# Sheet1.net
KiCad netlist of a schematic drawn in Altium Designer
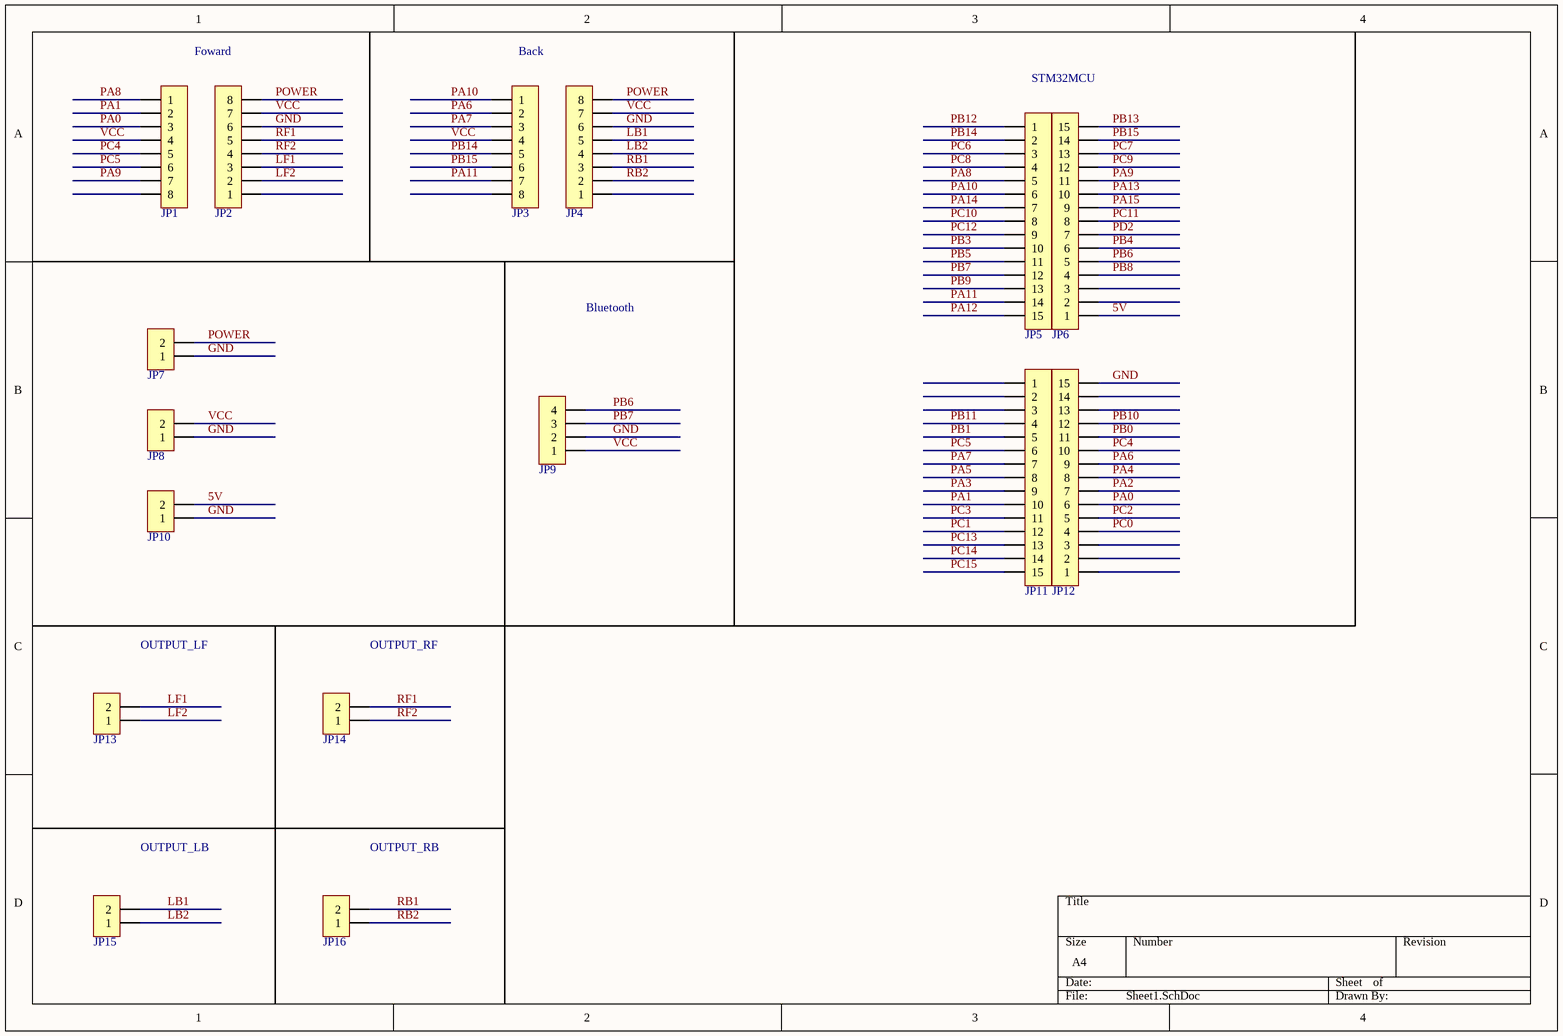
[diagram p0: Sheet1.SchDoc]

(export (version "E")
  (design (tool "Eeschema 10.0.6"))
  (components
    (comp (ref "JP1")
      (value "HDR-1X8")
      (footprint "Fe-HDR1X8/2.54-S")
      (description "8P接插件")
      (fields (field (name "版权归属") "源创客"))
      (libsource (lib "4.5   - 接插件-脚距2.54") (part "Header 8"))
    )
    (comp (ref "JP2")
      (value "HDR-1X8")
      (footprint "Fe-HDR1X8/2.54-S")
      (description "8P接插件")
      (fields (field (name "版权归属") "源创客"))
      (libsource (lib "") (part "Header 8_1"))
    )
    (comp (ref "JP3")
      (value "HDR-1X8")
      (footprint "Fe-HDR1X8/2.54-S")
      (description "8P接插件")
      (fields (field (name "版权归属") "源创客"))
      (libsource (lib "4.5   - 接插件-脚距2.54") (part "Header 8"))
    )
    (comp (ref "JP4")
      (value "HDR-1X8")
      (footprint "Fe-HDR1X8/2.54-S")
      (description "8P接插件")
      (fields (field (name "版权归属") "源创客"))
      (libsource (lib "") (part "Header 8_1"))
    )
    (comp (ref "JP5")
      (value "HDR-1X15")
      (footprint "Fe-HDR1X15/2.54-S")
      (description "15P接插件")
      (fields (field (name "版权归属") "源创客"))
      (libsource (lib "") (part "Header 15_1"))
    )
    (comp (ref "JP6")
      (value "HDR-1X15")
      (footprint "Fe-HDR1X15/2.54-S")
      (description "15P接插件")
      (fields (field (name "版权归属") "源创客"))
      (libsource (lib "4.5   - 接插件-脚距2.54") (part "Header 15"))
    )
    (comp (ref "JP7")
      (value "HDR-1X2")
      (footprint "Fe-HDR1X2/2.54-S")
      (description "2P接插件")
      (fields (field (name "版权归属") "源创客"))
      (libsource (lib "4.5   - 接插件-脚距2.54") (part "Header 2"))
    )
    (comp (ref "JP8")
      (value "HDR-1X2")
      (footprint "Fe-HDR1X2/2.54-S")
      (description "2P接插件")
      (fields (field (name "版权归属") "源创客"))
      (libsource (lib "4.5   - 接插件-脚距2.54") (part "Header 2"))
    )
    (comp (ref "JP9")
      (value "HDR-1X4")
      (footprint "Fe-HDR1X4/2.54-S")
      (description "4P接插件")
      (fields (field (name "版权归属") "源创客"))
      (libsource (lib "4.5   - 接插件-脚距2.54") (part "Header 4"))
    )
    (comp (ref "JP10")
      (value "HDR-1X2")
      (footprint "Fe-HDR1X2/2.54-S")
      (description "2P接插件")
      (fields (field (name "版权归属") "源创客"))
      (libsource (lib "4.5   - 接插件-脚距2.54") (part "Header 2"))
    )
    (comp (ref "JP11")
      (value "HDR-1X15")
      (footprint "Fe-HDR1X15/2.54-S")
      (description "15P接插件")
      (fields (field (name "版权归属") "源创客"))
      (libsource (lib "") (part "Header 15_1"))
    )
    (comp (ref "JP12")
      (value "HDR-1X15")
      (footprint "Fe-HDR1X15/2.54-S")
      (description "15P接插件")
      (fields (field (name "版权归属") "源创客"))
      (libsource (lib "4.5   - 接插件-脚距2.54") (part "Header 15"))
    )
    (comp (ref "JP13")
      (value "HDR-1X2")
      (footprint "Fe-HDR1X2/2.54-S")
      (description "2P接插件")
      (fields (field (name "版权归属") "源创客"))
      (libsource (lib "4.5   - 接插件-脚距2.54") (part "Header 2"))
    )
    (comp (ref "JP14")
      (value "HDR-1X2")
      (footprint "Fe-HDR1X2/2.54-S")
      (description "2P接插件")
      (fields (field (name "版权归属") "源创客"))
      (libsource (lib "4.5   - 接插件-脚距2.54") (part "Header 2"))
    )
    (comp (ref "JP15")
      (value "HDR-1X2")
      (footprint "Fe-HDR1X2/2.54-S")
      (description "2P接插件")
      (fields (field (name "版权归属") "源创客"))
      (libsource (lib "4.5   - 接插件-脚距2.54") (part "Header 2"))
    )
    (comp (ref "JP16")
      (value "HDR-1X2")
      (footprint "Fe-HDR1X2/2.54-S")
      (description "2P接插件")
      (fields (field (name "版权归属") "源创客"))
      (libsource (lib "4.5   - 接插件-脚距2.54") (part "Header 2"))
    )
  )
  (nets
    (net (code "1") (name "/5V") (class "Default")
      (node (ref "JP10") (pin "2") (pinfunction "2_2") (pintype "passive"))
      (node (ref "JP6") (pin "1") (pinfunction "1_1") (pintype "passive"))
    )
    (net (code "2") (name "/GND") (class "Default")
      (node (ref "JP10") (pin "1") (pinfunction "1_1") (pintype "passive"))
      (node (ref "JP12") (pin "15") (pinfunction "15_15") (pintype "passive"))
      (node (ref "JP2") (pin "6") (pinfunction "6_6") (pintype "passive"))
      (node (ref "JP4") (pin "6") (pinfunction "6_6") (pintype "passive"))
      (node (ref "JP7") (pin "1") (pinfunction "1_1") (pintype "passive"))
      (node (ref "JP8") (pin "1") (pinfunction "1_1") (pintype "passive"))
      (node (ref "JP9") (pin "2") (pinfunction "2_2") (pintype "passive"))
    )
    (net (code "3") (name "/LB1") (class "Default")
      (node (ref "JP15") (pin "2") (pinfunction "2_2") (pintype "passive"))
      (node (ref "JP4") (pin "5") (pinfunction "5_5") (pintype "passive"))
    )
    (net (code "4") (name "/LB2") (class "Default")
      (node (ref "JP15") (pin "1") (pinfunction "1_1") (pintype "passive"))
      (node (ref "JP4") (pin "4") (pinfunction "4_4") (pintype "passive"))
    )
    (net (code "5") (name "/LF1") (class "Default")
      (node (ref "JP13") (pin "2") (pinfunction "2_2") (pintype "passive"))
      (node (ref "JP2") (pin "3") (pinfunction "3_3") (pintype "passive"))
    )
    (net (code "6") (name "/LF2") (class "Default")
      (node (ref "JP13") (pin "1") (pinfunction "1_1") (pintype "passive"))
      (node (ref "JP2") (pin "2") (pinfunction "2_2") (pintype "passive"))
    )
    (net (code "7") (name "/PA0") (class "Default")
      (node (ref "JP1") (pin "3") (pinfunction "3_3") (pintype "passive"))
      (node (ref "JP12") (pin "6") (pinfunction "6_6") (pintype "passive"))
    )
    (net (code "8") (name "/PA1") (class "Default")
      (node (ref "JP1") (pin "2") (pinfunction "2_2") (pintype "passive"))
      (node (ref "JP11") (pin "10") (pinfunction "10_10") (pintype "passive"))
    )
    (net (code "9") (name "/PA2") (class "Default")
      (node (ref "JP12") (pin "7") (pinfunction "7_7") (pintype "passive"))
    )
    (net (code "10") (name "/PA3") (class "Default")
      (node (ref "JP11") (pin "9") (pinfunction "9_9") (pintype "passive"))
    )
    (net (code "11") (name "/PA4") (class "Default")
      (node (ref "JP12") (pin "8") (pinfunction "8_8") (pintype "passive"))
    )
    (net (code "12") (name "/PA5") (class "Default")
      (node (ref "JP11") (pin "8") (pinfunction "8_8") (pintype "passive"))
    )
    (net (code "13") (name "/PA6") (class "Default")
      (node (ref "JP12") (pin "9") (pinfunction "9_9") (pintype "passive"))
      (node (ref "JP3") (pin "2") (pinfunction "2_2") (pintype "passive"))
    )
    (net (code "14") (name "/PA7") (class "Default")
      (node (ref "JP11") (pin "7") (pinfunction "7_7") (pintype "passive"))
      (node (ref "JP3") (pin "3") (pinfunction "3_3") (pintype "passive"))
    )
    (net (code "15") (name "/PA8") (class "Default")
      (node (ref "JP1") (pin "1") (pinfunction "1_1") (pintype "passive"))
      (node (ref "JP5") (pin "5") (pinfunction "5_5") (pintype "passive"))
    )
    (net (code "16") (name "/PA9") (class "Default")
      (node (ref "JP1") (pin "7") (pinfunction "7_7") (pintype "passive"))
      (node (ref "JP6") (pin "11") (pinfunction "11_11") (pintype "passive"))
    )
    (net (code "17") (name "/PA10") (class "Default")
      (node (ref "JP3") (pin "1") (pinfunction "1_1") (pintype "passive"))
      (node (ref "JP5") (pin "6") (pinfunction "6_6") (pintype "passive"))
    )
    (net (code "18") (name "/PA11") (class "Default")
      (node (ref "JP3") (pin "7") (pinfunction "7_7") (pintype "passive"))
      (node (ref "JP5") (pin "14") (pinfunction "14_14") (pintype "passive"))
    )
    (net (code "19") (name "/PA12") (class "Default")
      (node (ref "JP5") (pin "15") (pinfunction "15_15") (pintype "passive"))
    )
    (net (code "20") (name "/PA13") (class "Default")
      (node (ref "JP6") (pin "10") (pinfunction "10_10") (pintype "passive"))
    )
    (net (code "21") (name "/PA14") (class "Default")
      (node (ref "JP5") (pin "7") (pinfunction "7_7") (pintype "passive"))
    )
    (net (code "22") (name "/PA15") (class "Default")
      (node (ref "JP6") (pin "9") (pinfunction "9_9") (pintype "passive"))
    )
    (net (code "23") (name "/PB0") (class "Default")
      (node (ref "JP12") (pin "11") (pinfunction "11_11") (pintype "passive"))
    )
    (net (code "24") (name "/PB1") (class "Default")
      (node (ref "JP11") (pin "5") (pinfunction "5_5") (pintype "passive"))
    )
    (net (code "25") (name "/PB3") (class "Default")
      (node (ref "JP5") (pin "10") (pinfunction "10_10") (pintype "passive"))
    )
    (net (code "26") (name "/PB4") (class "Default")
      (node (ref "JP6") (pin "6") (pinfunction "6_6") (pintype "passive"))
    )
    (net (code "27") (name "/PB5") (class "Default")
      (node (ref "JP5") (pin "11") (pinfunction "11_11") (pintype "passive"))
    )
    (net (code "28") (name "/PB6") (class "Default")
      (node (ref "JP6") (pin "5") (pinfunction "5_5") (pintype "passive"))
      (node (ref "JP9") (pin "4") (pinfunction "4_4") (pintype "passive"))
    )
    (net (code "29") (name "/PB7") (class "Default")
      (node (ref "JP5") (pin "12") (pinfunction "12_12") (pintype "passive"))
      (node (ref "JP9") (pin "3") (pinfunction "3_3") (pintype "passive"))
    )
    (net (code "30") (name "/PB8") (class "Default")
      (node (ref "JP6") (pin "4") (pinfunction "4_4") (pintype "passive"))
    )
    (net (code "31") (name "/PB9") (class "Default")
      (node (ref "JP5") (pin "13") (pinfunction "13_13") (pintype "passive"))
    )
    (net (code "32") (name "/PB10") (class "Default")
      (node (ref "JP12") (pin "12") (pinfunction "12_12") (pintype "passive"))
    )
    (net (code "33") (name "/PB11") (class "Default")
      (node (ref "JP11") (pin "4") (pinfunction "4_4") (pintype "passive"))
    )
    (net (code "34") (name "/PB12") (class "Default")
      (node (ref "JP5") (pin "1") (pinfunction "1_1") (pintype "passive"))
    )
    (net (code "35") (name "/PB13") (class "Default")
      (node (ref "JP6") (pin "15") (pinfunction "15_15") (pintype "passive"))
    )
    (net (code "36") (name "/PB14") (class "Default")
      (node (ref "JP3") (pin "5") (pinfunction "5_5") (pintype "passive"))
      (node (ref "JP5") (pin "2") (pinfunction "2_2") (pintype "passive"))
    )
    (net (code "37") (name "/PB15") (class "Default")
      (node (ref "JP3") (pin "6") (pinfunction "6_6") (pintype "passive"))
      (node (ref "JP6") (pin "14") (pinfunction "14_14") (pintype "passive"))
    )
    (net (code "38") (name "/PC0") (class "Default")
      (node (ref "JP12") (pin "4") (pinfunction "4_4") (pintype "passive"))
    )
    (net (code "39") (name "/PC1") (class "Default")
      (node (ref "JP11") (pin "12") (pinfunction "12_12") (pintype "passive"))
    )
    (net (code "40") (name "/PC2") (class "Default")
      (node (ref "JP12") (pin "5") (pinfunction "5_5") (pintype "passive"))
    )
    (net (code "41") (name "/PC3") (class "Default")
      (node (ref "JP11") (pin "11") (pinfunction "11_11") (pintype "passive"))
    )
    (net (code "42") (name "/PC4") (class "Default")
      (node (ref "JP1") (pin "5") (pinfunction "5_5") (pintype "passive"))
      (node (ref "JP12") (pin "10") (pinfunction "10_10") (pintype "passive"))
    )
    (net (code "43") (name "/PC5") (class "Default")
      (node (ref "JP1") (pin "6") (pinfunction "6_6") (pintype "passive"))
      (node (ref "JP11") (pin "6") (pinfunction "6_6") (pintype "passive"))
    )
    (net (code "44") (name "/PC6") (class "Default")
      (node (ref "JP5") (pin "3") (pinfunction "3_3") (pintype "passive"))
    )
    (net (code "45") (name "/PC7") (class "Default")
      (node (ref "JP6") (pin "13") (pinfunction "13_13") (pintype "passive"))
    )
    (net (code "46") (name "/PC8") (class "Default")
      (node (ref "JP5") (pin "4") (pinfunction "4_4") (pintype "passive"))
    )
    (net (code "47") (name "/PC9") (class "Default")
      (node (ref "JP6") (pin "12") (pinfunction "12_12") (pintype "passive"))
    )
    (net (code "48") (name "/PC10") (class "Default")
      (node (ref "JP5") (pin "8") (pinfunction "8_8") (pintype "passive"))
    )
    (net (code "49") (name "/PC11") (class "Default")
      (node (ref "JP6") (pin "8") (pinfunction "8_8") (pintype "passive"))
    )
    (net (code "50") (name "/PC12") (class "Default")
      (node (ref "JP5") (pin "9") (pinfunction "9_9") (pintype "passive"))
    )
    (net (code "51") (name "/PC13") (class "Default")
      (node (ref "JP11") (pin "13") (pinfunction "13_13") (pintype "passive"))
    )
    (net (code "52") (name "/PC14") (class "Default")
      (node (ref "JP11") (pin "14") (pinfunction "14_14") (pintype "passive"))
    )
    (net (code "53") (name "/PC15") (class "Default")
      (node (ref "JP11") (pin "15") (pinfunction "15_15") (pintype "passive"))
    )
    (net (code "54") (name "/PD2") (class "Default")
      (node (ref "JP6") (pin "7") (pinfunction "7_7") (pintype "passive"))
    )
    (net (code "55") (name "/POWER") (class "Default")
      (node (ref "JP2") (pin "8") (pinfunction "8_8") (pintype "passive"))
      (node (ref "JP4") (pin "8") (pinfunction "8_8") (pintype "passive"))
      (node (ref "JP7") (pin "2") (pinfunction "2_2") (pintype "passive"))
    )
    (net (code "56") (name "/RB1") (class "Default")
      (node (ref "JP16") (pin "2") (pinfunction "2_2") (pintype "passive"))
      (node (ref "JP4") (pin "3") (pinfunction "3_3") (pintype "passive"))
    )
    (net (code "57") (name "/RB2") (class "Default")
      (node (ref "JP16") (pin "1") (pinfunction "1_1") (pintype "passive"))
      (node (ref "JP4") (pin "2") (pinfunction "2_2") (pintype "passive"))
    )
    (net (code "58") (name "/RF1") (class "Default")
      (node (ref "JP14") (pin "2") (pinfunction "2_2") (pintype "passive"))
      (node (ref "JP2") (pin "5") (pinfunction "5_5") (pintype "passive"))
    )
    (net (code "59") (name "/RF2") (class "Default")
      (node (ref "JP14") (pin "1") (pinfunction "1_1") (pintype "passive"))
      (node (ref "JP2") (pin "4") (pinfunction "4_4") (pintype "passive"))
    )
    (net (code "60") (name "/VCC") (class "Default")
      (node (ref "JP1") (pin "4") (pinfunction "4_4") (pintype "passive"))
      (node (ref "JP2") (pin "7") (pinfunction "7_7") (pintype "passive"))
      (node (ref "JP3") (pin "4") (pinfunction "4_4") (pintype "passive"))
      (node (ref "JP4") (pin "7") (pinfunction "7_7") (pintype "passive"))
      (node (ref "JP8") (pin "2") (pinfunction "2_2") (pintype "passive"))
      (node (ref "JP9") (pin "1") (pinfunction "1_1") (pintype "passive"))
    )
    (net (code "61") (name "unconnected-(JP1-Pad8)") (class "Default")
      (node (ref "JP1") (pin "8") (pinfunction "8_8") (pintype "passive"))
    )
    (net (code "62") (name "unconnected-(JP2-Pad1)") (class "Default")
      (node (ref "JP2") (pin "1") (pinfunction "1_1") (pintype "passive"))
    )
    (net (code "63") (name "unconnected-(JP3-Pad8)") (class "Default")
      (node (ref "JP3") (pin "8") (pinfunction "8_8") (pintype "passive"))
    )
    (net (code "64") (name "unconnected-(JP4-Pad1)") (class "Default")
      (node (ref "JP4") (pin "1") (pinfunction "1_1") (pintype "passive"))
    )
    (net (code "65") (name "unconnected-(JP6-Pad2)") (class "Default")
      (node (ref "JP6") (pin "2") (pinfunction "2_2") (pintype "passive"))
    )
    (net (code "66") (name "unconnected-(JP6-Pad3)") (class "Default")
      (node (ref "JP6") (pin "3") (pinfunction "3_3") (pintype "passive"))
    )
    (net (code "67") (name "unconnected-(JP11-Pad1)") (class "Default")
      (node (ref "JP11") (pin "1") (pinfunction "1_1") (pintype "passive"))
    )
    (net (code "68") (name "unconnected-(JP11-Pad2)") (class "Default")
      (node (ref "JP11") (pin "2") (pinfunction "2_2") (pintype "passive"))
    )
    (net (code "69") (name "unconnected-(JP11-Pad3)") (class "Default")
      (node (ref "JP11") (pin "3") (pinfunction "3_3") (pintype "passive"))
    )
    (net (code "70") (name "unconnected-(JP12-Pad1)") (class "Default")
      (node (ref "JP12") (pin "1") (pinfunction "1_1") (pintype "passive"))
    )
    (net (code "71") (name "unconnected-(JP12-Pad2)") (class "Default")
      (node (ref "JP12") (pin "2") (pinfunction "2_2") (pintype "passive"))
    )
    (net (code "72") (name "unconnected-(JP12-Pad3)") (class "Default")
      (node (ref "JP12") (pin "3") (pinfunction "3_3") (pintype "passive"))
    )
    (net (code "73") (name "unconnected-(JP12-Pad13)") (class "Default")
      (node (ref "JP12") (pin "13") (pinfunction "13_13") (pintype "passive"))
    )
    (net (code "74") (name "unconnected-(JP12-Pad14)") (class "Default")
      (node (ref "JP12") (pin "14") (pinfunction "14_14") (pintype "passive"))
    )
  )
)
